# mx232JoeyAngShiYuan.net
KiCad netlist of a schematic drawn in EAGLE
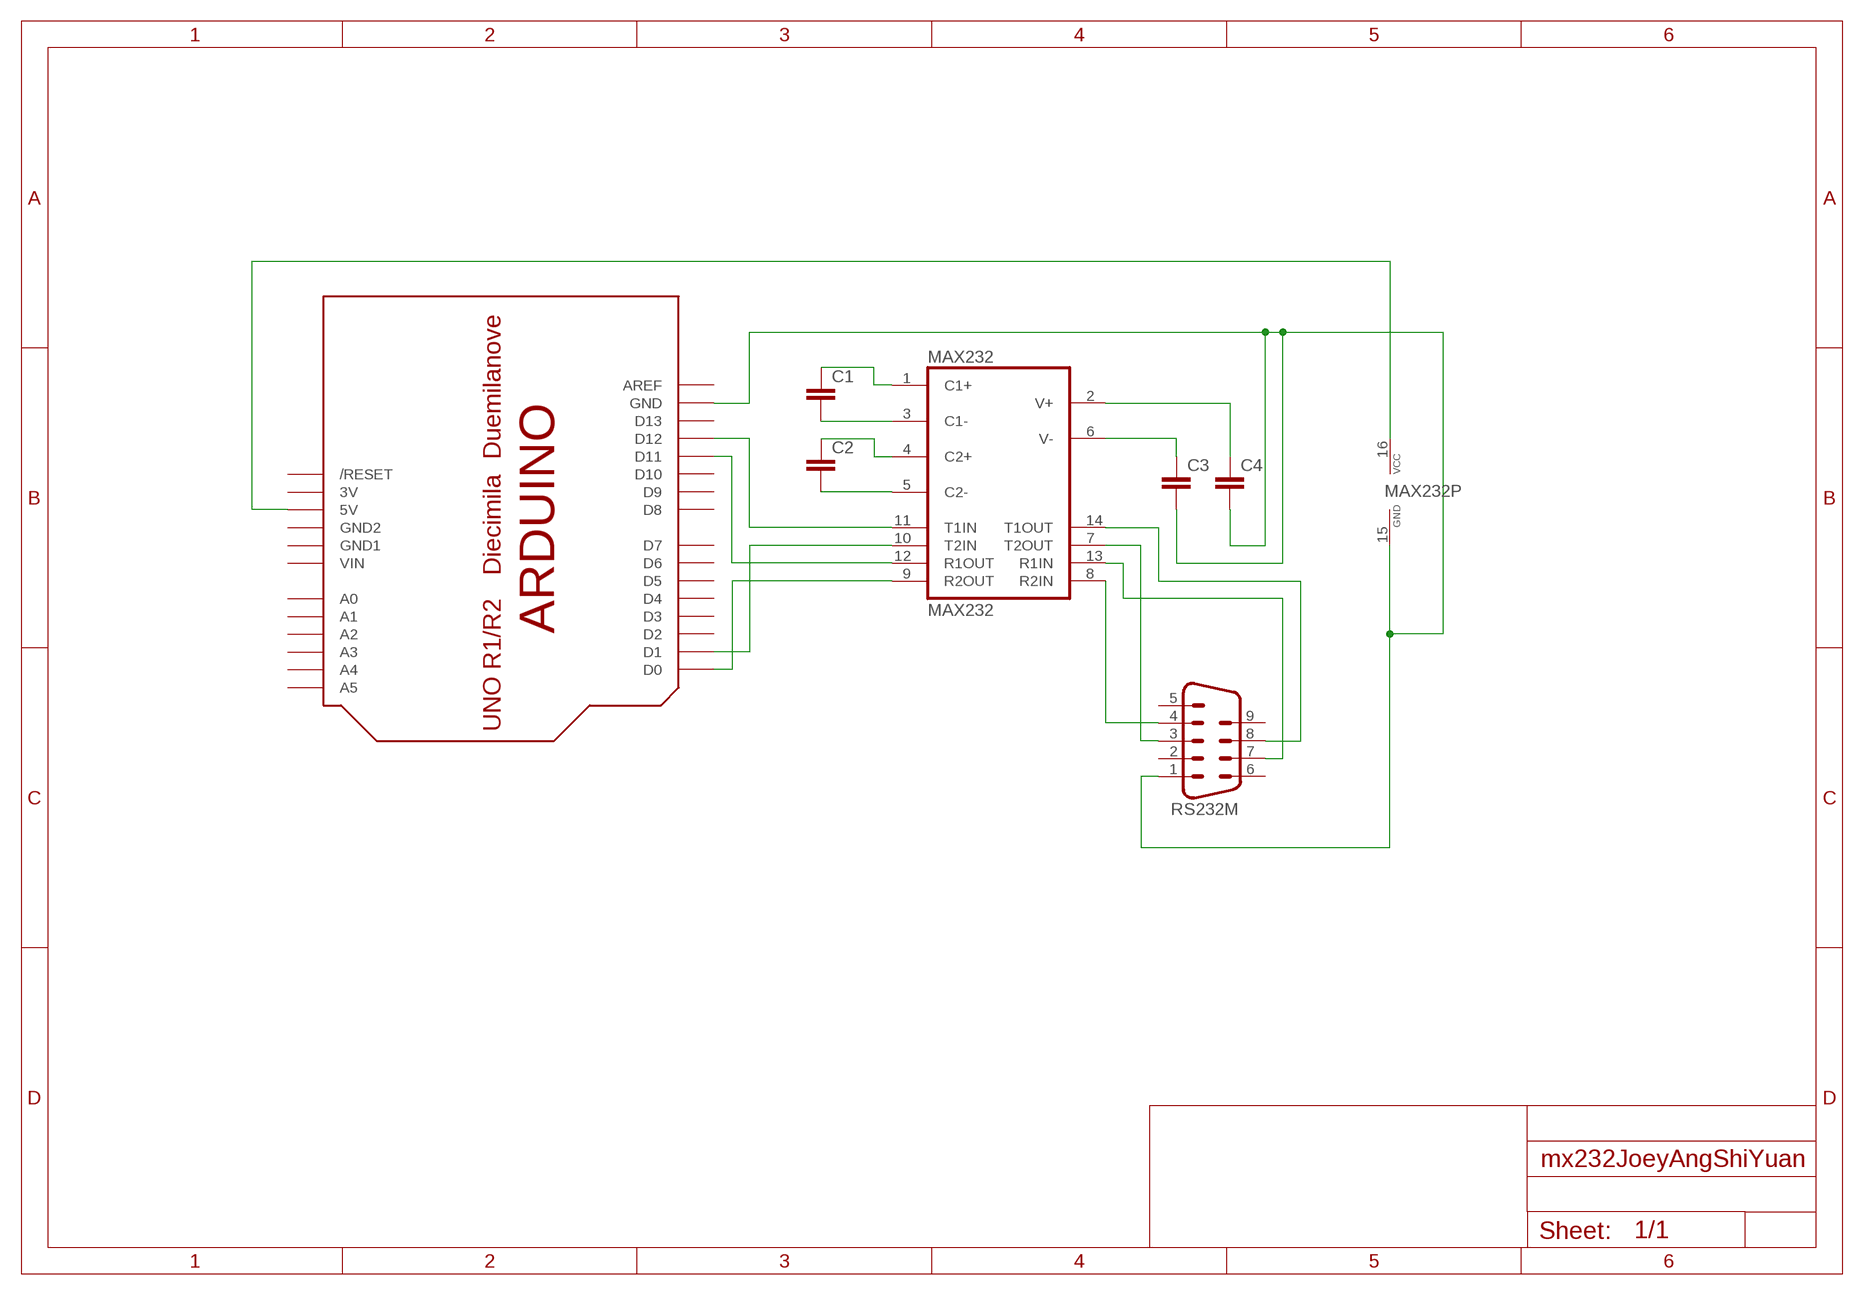
[diagram p0: schematic, sheet 1]

(export (version "E")
  (design (tool "Eeschema 10.0.6"))
  (components
    (comp (ref "C1")
      (value "C2,5-3")
      (footprint "eagle-import:C2.5-3")
      (libsource (lib "eagle-import") (part "C2,5-3"))
    )
    (comp (ref "C2")
      (value "C2,5-3")
      (footprint "eagle-import:C2.5-3")
      (libsource (lib "eagle-import") (part "C2,5-3"))
    )
    (comp (ref "C3")
      (value "C2,5-3")
      (footprint "eagle-import:C2.5-3")
      (libsource (lib "eagle-import") (part "C2,5-3"))
    )
    (comp (ref "C4")
      (value "C2,5-3")
      (footprint "eagle-import:C2.5-3")
      (libsource (lib "eagle-import") (part "C2,5-3"))
    )
    (comp (ref "LEONARDO-SHIELD")
      (value "ARDUINO-NOHOLE")
      (footprint "eagle-import:ARDUINO-NOHOLE")
      (libsource (lib "eagle-import") (part "ARDUINO-NOHOLE"))
    )
    (comp (ref "MAX232")
      (value "MAX232")
      (footprint "eagle-import:DIL16")
      (fields (field (name "MF") "MAXIM") (field (name "MPN") "MAX232ACPE+"))
      (libsource (lib "eagle-import") (part "MAX232"))
    )
    (comp (ref "RS232M")
      (value "M09HP")
      (footprint "eagle-import:M09HP")
      (libsource (lib "eagle-import") (part "M09HP"))
    )
  )
  (nets
    (net (code "1") (name "/3V") (class "Default")
      (node (ref "LEONARDO-SHIELD") (pin "3V") (pinfunction "3V_3V") (pintype "power_in"))
    )
    (net (code "2") (name "/GND1") (class "Default")
      (node (ref "LEONARDO-SHIELD") (pin "GND1") (pinfunction "GND1_GND1") (pintype "power_in"))
    )
    (net (code "3") (name "/GND2") (class "Default")
      (node (ref "LEONARDO-SHIELD") (pin "GND2") (pinfunction "GND2_GND2") (pintype "power_in"))
    )
    (net (code "4") (name "/VIN") (class "Default")
      (node (ref "LEONARDO-SHIELD") (pin "VIN") (pinfunction "VIN_VIN") (pintype "power_in"))
    )
    (net (code "5") (name "Net-(MAX232A-C1+)") (class "Default")
      (node (ref "C1") (pin "1") (pinfunction "1_1") (pintype "passive"))
      (node (ref "MAX232") (pin "1") (pinfunction "C1+_1") (pintype "bidirectional"))
    )
    (net (code "6") (name "Net-(MAX232A-C1-)") (class "Default")
      (node (ref "C1") (pin "2") (pinfunction "2_2") (pintype "passive"))
      (node (ref "MAX232") (pin "3") (pinfunction "C1-_3") (pintype "bidirectional"))
    )
    (net (code "7") (name "Net-(MAX232A-C2+)") (class "Default")
      (node (ref "C2") (pin "1") (pinfunction "1_1") (pintype "passive"))
      (node (ref "MAX232") (pin "4") (pinfunction "C2+_4") (pintype "bidirectional"))
    )
    (net (code "8") (name "Net-(MAX232A-C2-)") (class "Default")
      (node (ref "C2") (pin "2") (pinfunction "2_2") (pintype "passive"))
      (node (ref "MAX232") (pin "5") (pinfunction "C2-_5") (pintype "bidirectional"))
    )
    (net (code "9") (name "Net-(MAX232A-R1IN)") (class "Default")
      (node (ref "MAX232") (pin "13") (pinfunction "R1IN_13") (pintype "input"))
      (node (ref "RS232M") (pin "7") (pinfunction "7_7") (pintype "passive"))
    )
    (net (code "10") (name "Net-(MAX232A-R1OUT)") (class "Default")
      (node (ref "LEONARDO-SHIELD") (pin "D11") (pinfunction "D11_D11") (pintype "bidirectional"))
      (node (ref "MAX232") (pin "12") (pinfunction "R1OUT_12") (pintype "output"))
    )
    (net (code "11") (name "Net-(MAX232A-R2IN)") (class "Default")
      (node (ref "MAX232") (pin "8") (pinfunction "R2IN_8") (pintype "input"))
      (node (ref "RS232M") (pin "4") (pinfunction "4_4") (pintype "passive"))
    )
    (net (code "12") (name "Net-(MAX232A-R2OUT)") (class "Default")
      (node (ref "LEONARDO-SHIELD") (pin "D0") (pinfunction "D0_D0") (pintype "bidirectional"))
      (node (ref "MAX232") (pin "9") (pinfunction "R2OUT_9") (pintype "output"))
    )
    (net (code "13") (name "Net-(MAX232A-T1IN)") (class "Default")
      (node (ref "LEONARDO-SHIELD") (pin "D12") (pinfunction "D12_D12") (pintype "bidirectional"))
      (node (ref "MAX232") (pin "11") (pinfunction "T1IN_11") (pintype "input"))
    )
    (net (code "14") (name "Net-(MAX232A-T1OUT)") (class "Default")
      (node (ref "MAX232") (pin "14") (pinfunction "T1OUT_14") (pintype "output"))
      (node (ref "RS232M") (pin "8") (pinfunction "8_8") (pintype "passive"))
    )
    (net (code "15") (name "Net-(MAX232A-T2IN)") (class "Default")
      (node (ref "LEONARDO-SHIELD") (pin "D1") (pinfunction "D1_D1") (pintype "bidirectional"))
      (node (ref "MAX232") (pin "10") (pinfunction "T2IN_10") (pintype "input"))
    )
    (net (code "16") (name "Net-(MAX232A-T2OUT)") (class "Default")
      (node (ref "MAX232") (pin "7") (pinfunction "T2OUT_7") (pintype "output"))
      (node (ref "RS232M") (pin "3") (pinfunction "3_3") (pintype "passive"))
    )
    (net (code "17") (name "Net-(MAX232A-V+)") (class "Default")
      (node (ref "C4") (pin "1") (pinfunction "1_1") (pintype "passive"))
      (node (ref "MAX232") (pin "2") (pinfunction "V+_2") (pintype "bidirectional"))
    )
    (net (code "18") (name "Net-(MAX232A-V-)") (class "Default")
      (node (ref "C3") (pin "1") (pinfunction "1_1") (pintype "passive"))
      (node (ref "MAX232") (pin "6") (pinfunction "V-_6") (pintype "bidirectional"))
    )
    (net (code "19") (name "Net-(MAX232B-GND)") (class "Default")
      (node (ref "C3") (pin "2") (pinfunction "2_2") (pintype "passive"))
      (node (ref "C4") (pin "2") (pinfunction "2_2") (pintype "passive"))
      (node (ref "LEONARDO-SHIELD") (pin "GND") (pinfunction "GND_GND") (pintype "power_in"))
      (node (ref "MAX232") (pin "15") (pinfunction "GND_15") (pintype "power_in"))
      (node (ref "RS232M") (pin "1") (pinfunction "1_1") (pintype "passive"))
    )
    (net (code "20") (name "Net-(MAX232B-VCC)") (class "Default")
      (node (ref "LEONARDO-SHIELD") (pin "5V") (pinfunction "5V_5V") (pintype "power_in"))
      (node (ref "MAX232") (pin "16") (pinfunction "VCC_16") (pintype "power_in"))
    )
    (net (code "21") (name "unconnected-(LEONARDO-SHIELD-PadA0)") (class "Default")
      (node (ref "LEONARDO-SHIELD") (pin "A0") (pinfunction "A0_A0") (pintype "bidirectional"))
    )
    (net (code "22") (name "unconnected-(LEONARDO-SHIELD-PadA1)") (class "Default")
      (node (ref "LEONARDO-SHIELD") (pin "A1") (pinfunction "A1_A1") (pintype "bidirectional"))
    )
    (net (code "23") (name "unconnected-(LEONARDO-SHIELD-PadA2)") (class "Default")
      (node (ref "LEONARDO-SHIELD") (pin "A2") (pinfunction "A2_A2") (pintype "bidirectional"))
    )
    (net (code "24") (name "unconnected-(LEONARDO-SHIELD-PadA3)") (class "Default")
      (node (ref "LEONARDO-SHIELD") (pin "A3") (pinfunction "A3_A3") (pintype "bidirectional"))
    )
    (net (code "25") (name "unconnected-(LEONARDO-SHIELD-PadA4)") (class "Default")
      (node (ref "LEONARDO-SHIELD") (pin "A4") (pinfunction "A4_A4") (pintype "bidirectional"))
    )
    (net (code "26") (name "unconnected-(LEONARDO-SHIELD-PadA5)") (class "Default")
      (node (ref "LEONARDO-SHIELD") (pin "A5") (pinfunction "A5_A5") (pintype "bidirectional"))
    )
    (net (code "27") (name "unconnected-(LEONARDO-SHIELD-PadAREF)") (class "Default")
      (node (ref "LEONARDO-SHIELD") (pin "AREF") (pinfunction "AREF_AREF") (pintype "bidirectional"))
    )
    (net (code "28") (name "unconnected-(LEONARDO-SHIELD-PadD2)") (class "Default")
      (node (ref "LEONARDO-SHIELD") (pin "D2") (pinfunction "D2_D2") (pintype "bidirectional"))
    )
    (net (code "29") (name "unconnected-(LEONARDO-SHIELD-PadD3)") (class "Default")
      (node (ref "LEONARDO-SHIELD") (pin "D3") (pinfunction "D3_D3") (pintype "bidirectional"))
    )
    (net (code "30") (name "unconnected-(LEONARDO-SHIELD-PadD4)") (class "Default")
      (node (ref "LEONARDO-SHIELD") (pin "D4") (pinfunction "D4_D4") (pintype "bidirectional"))
    )
    (net (code "31") (name "unconnected-(LEONARDO-SHIELD-PadD5)") (class "Default")
      (node (ref "LEONARDO-SHIELD") (pin "D5") (pinfunction "D5_D5") (pintype "bidirectional"))
    )
    (net (code "32") (name "unconnected-(LEONARDO-SHIELD-PadD6)") (class "Default")
      (node (ref "LEONARDO-SHIELD") (pin "D6") (pinfunction "D6_D6") (pintype "bidirectional"))
    )
    (net (code "33") (name "unconnected-(LEONARDO-SHIELD-PadD7)") (class "Default")
      (node (ref "LEONARDO-SHIELD") (pin "D7") (pinfunction "D7_D7") (pintype "bidirectional"))
    )
    (net (code "34") (name "unconnected-(LEONARDO-SHIELD-PadD8)") (class "Default")
      (node (ref "LEONARDO-SHIELD") (pin "D8") (pinfunction "D8_D8") (pintype "bidirectional"))
    )
    (net (code "35") (name "unconnected-(LEONARDO-SHIELD-PadD9)") (class "Default")
      (node (ref "LEONARDO-SHIELD") (pin "D9") (pinfunction "D9_D9") (pintype "bidirectional"))
    )
    (net (code "36") (name "unconnected-(LEONARDO-SHIELD-PadD10)") (class "Default")
      (node (ref "LEONARDO-SHIELD") (pin "D10") (pinfunction "D10_D10") (pintype "bidirectional"))
    )
    (net (code "37") (name "unconnected-(LEONARDO-SHIELD-PadD13)") (class "Default")
      (node (ref "LEONARDO-SHIELD") (pin "D13") (pinfunction "D13_D13") (pintype "bidirectional"))
    )
    (net (code "38") (name "unconnected-(LEONARDO-SHIELD-{slash}RESET-PadRESET)") (class "Default")
      (node (ref "LEONARDO-SHIELD") (pin "RESET") (pinfunction "/RESET_RESET") (pintype "bidirectional"))
    )
    (net (code "39") (name "unconnected-(RS232M-Pad2)") (class "Default")
      (node (ref "RS232M") (pin "2") (pinfunction "2_2") (pintype "passive"))
    )
    (net (code "40") (name "unconnected-(RS232M-Pad5)") (class "Default")
      (node (ref "RS232M") (pin "5") (pinfunction "5_5") (pintype "passive"))
    )
    (net (code "41") (name "unconnected-(RS232M-Pad6)") (class "Default")
      (node (ref "RS232M") (pin "6") (pinfunction "6_6") (pintype "passive"))
    )
    (net (code "42") (name "unconnected-(RS232M-Pad9)") (class "Default")
      (node (ref "RS232M") (pin "9") (pinfunction "9_9") (pintype "passive"))
    )
  )
)
